# Sheet.net
KiCad netlist of a schematic drawn in Altium Designer
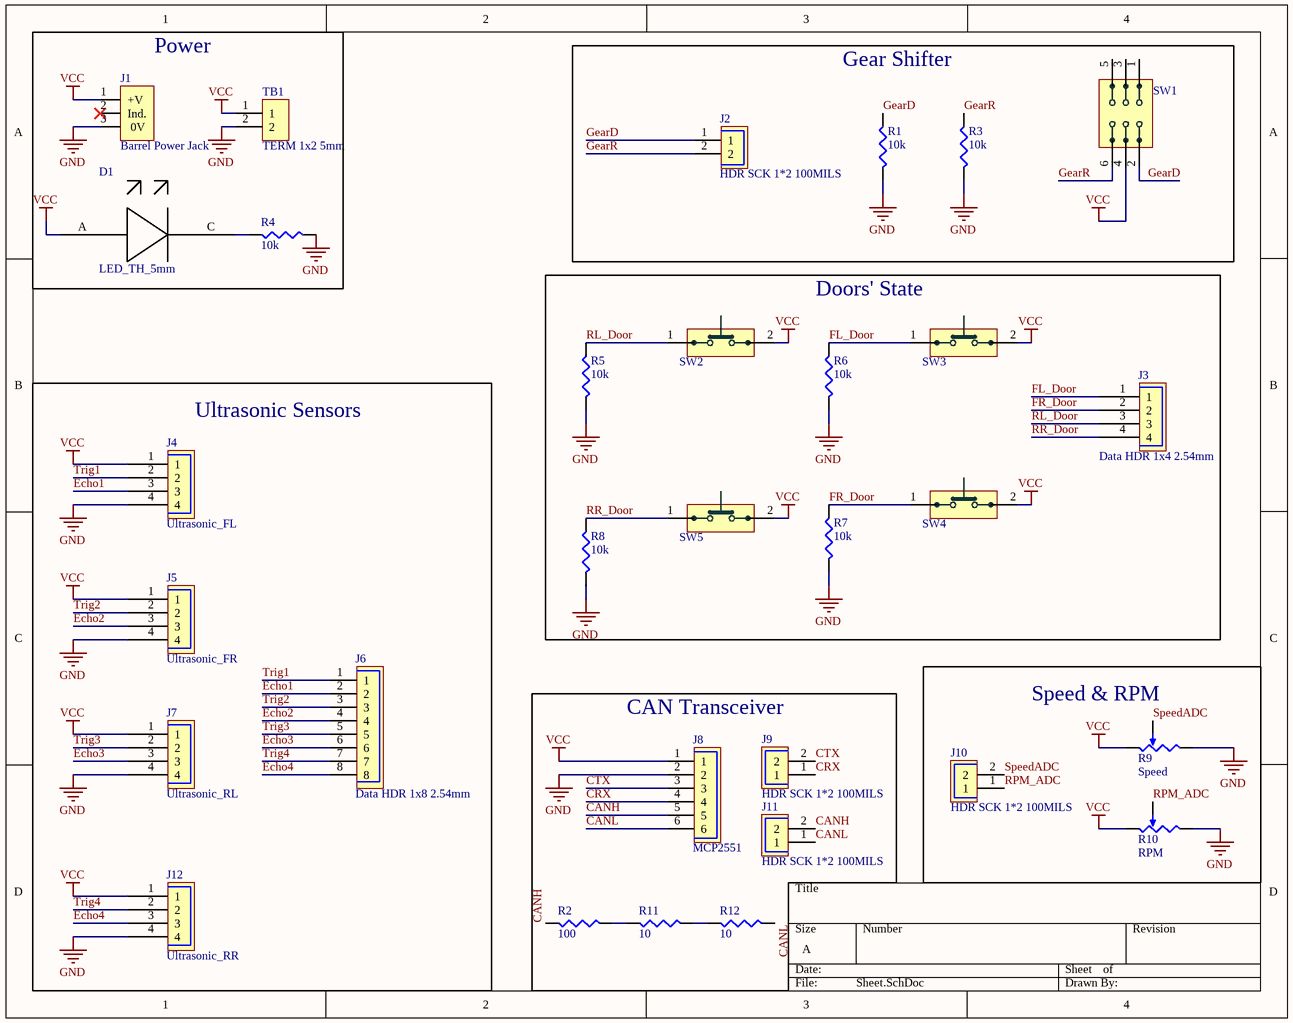
[diagram p0: Sheet.SchDoc]

(export (version "E")
  (design (tool "Eeschema 10.0.6"))
  (components
    (comp (ref "D1")
      (value "LED_TH_5mm")
      (footprint "LED_TH_5mm")
      (libsource (lib "Schlib") (part "LED_TH_5mm"))
    )
    (comp (ref "J1")
      (value "Barrel Power Jack")
      (footprint "pwr_Jack")
      (description "DC-Power Socket 12V 5A 2, 1mm Solder Eyel")
      (libsource (lib "CAD_Symbols") (part "Con-Jack"))
    )
    (comp (ref "J2")
      (value "HDR SCK 1*2 100MILS")
      (footprint "DHDR 1*2 2,54MM")
      (description "Conn Shrouded Header HDR 2 POS 2.54mm Solder ST Thru-Hole")
      (libsource (lib "") (part "2-Pin Data Connector_1"))
    )
    (comp (ref "J3")
      (value "Data HDR 1x4 2.54mm")
      (footprint "DHDR_1x4_2.54mm")
      (description "MTA-100 Series, 2.54mm Pitch 4 Way 1 RowStraight PCB Header, Solder Term, 5A")
      (libsource (lib "CAD_Symbols") (part "4-Pin Data Connector"))
    )
    (comp (ref "J4")
      (value "Ultrasonic_FL")
      (footprint "DHDR_1x4_2.54mm")
      (description "MTA-100 Series, 2.54mm Pitch 4 Way 1 RowStraight PCB Header, Solder Term, 5A")
      (libsource (lib "CAD_Symbols") (part "4-Pin Data Connector"))
    )
    (comp (ref "J5")
      (value "Ultrasonic_FR")
      (footprint "DHDR_1x4_2.54mm")
      (description "MTA-100 Series, 2.54mm Pitch 4 Way 1 RowStraight PCB Header, Solder Term, 5A")
      (libsource (lib "CAD_Symbols") (part "4-Pin Data Connector"))
    )
    (comp (ref "J6")
      (value "Data HDR 1x8 2.54mm")
      (footprint "DHDR_1x8_2.54mm")
      (description "CONN HEADER VERT 8POS .100 TIN")
      (libsource (lib "Schlib") (part "PinHeader_8Pin"))
    )
    (comp (ref "J7")
      (value "Ultrasonic_RL")
      (footprint "DHDR_1x4_2.54mm")
      (description "MTA-100 Series, 2.54mm Pitch 4 Way 1 RowStraight PCB Header, Solder Term, 5A")
      (libsource (lib "CAD_Symbols") (part "4-Pin Data Connector"))
    )
    (comp (ref "J8")
      (value "MCP2551")
      (footprint "DHDR_1x6_2.54mm")
      (description "CONN HEADER VERT 6POS .100 TIN")
      (libsource (lib "CAD_Symbols") (part "6-Pin Data Connector"))
    )
    (comp (ref "J9")
      (value "HDR SCK 1*2 100MILS")
      (footprint "DHDR 1*2 2,54MM")
      (description "Conn Shrouded Header HDR 2 POS 2.54mm Solder ST Thru-Hole")
      (libsource (lib "CAD_Symbols") (part "2-Pin Data Connector"))
    )
    (comp (ref "J10")
      (value "HDR SCK 1*2 100MILS")
      (footprint "DHDR 1*2 2,54MM")
      (description "Conn Shrouded Header HDR 2 POS 2.54mm Solder ST Thru-Hole")
      (libsource (lib "CAD_Symbols") (part "2-Pin Data Connector"))
    )
    (comp (ref "J11")
      (value "HDR SCK 1*2 100MILS")
      (footprint "DHDR 1*2 2,54MM")
      (description "Conn Shrouded Header HDR 2 POS 2.54mm Solder ST Thru-Hole")
      (libsource (lib "CAD_Symbols") (part "2-Pin Data Connector"))
    )
    (comp (ref "J12")
      (value "Ultrasonic_RR")
      (footprint "DHDR_1x4_2.54mm")
      (description "MTA-100 Series, 2.54mm Pitch 4 Way 1 RowStraight PCB Header, Solder Term, 5A")
      (libsource (lib "CAD_Symbols") (part "4-Pin Data Connector"))
    )
    (comp (ref "R1")
      (value "10k")
      (footprint "R_THT_CFR-25")
      (description "CFR Series 0.25 W 1 KOhm ±5 % -350 to 500 ppm/°C Carbon Film Resistor")
      (fields (field (name "TOLERANCE") "5%"))
      (libsource (lib "CAD_Symbols") (part "TH CFR-25 Resis"))
    )
    (comp (ref "R2")
      (value "100")
      (footprint "R_THT_CFR-25")
      (description "CFR Series 0.25 W 1 KOhm ±5 % -350 to 500 ppm/°C Carbon Film Resistor")
      (fields (field (name "TOLERANCE") "5%"))
      (libsource (lib "CAD_Symbols") (part "TH CFR-25 Resis"))
    )
    (comp (ref "R3")
      (value "10k")
      (footprint "R_THT_CFR-25")
      (description "CFR Series 0.25 W 1 KOhm ±5 % -350 to 500 ppm/°C Carbon Film Resistor")
      (fields (field (name "TOLERANCE") "5%"))
      (libsource (lib "CAD_Symbols") (part "TH CFR-25 Resis"))
    )
    (comp (ref "R4")
      (value "10k")
      (footprint "R_THT_CFR-25")
      (description "CFR Series 0.25 W 1 KOhm ±5 % -350 to 500 ppm/°C Carbon Film Resistor")
      (fields (field (name "TOLERANCE") "5%"))
      (libsource (lib "CAD_Symbols") (part "TH CFR-25 Resis"))
    )
    (comp (ref "R5")
      (value "10k")
      (footprint "R_THT_CFR-25")
      (description "CFR Series 0.25 W 1 KOhm ±5 % -350 to 500 ppm/°C Carbon Film Resistor")
      (fields (field (name "TOLERANCE") "5%"))
      (libsource (lib "CAD_Symbols") (part "TH CFR-25 Resis"))
    )
    (comp (ref "R6")
      (value "10k")
      (footprint "R_THT_CFR-25")
      (description "CFR Series 0.25 W 1 KOhm ±5 % -350 to 500 ppm/°C Carbon Film Resistor")
      (fields (field (name "TOLERANCE") "5%"))
      (libsource (lib "CAD_Symbols") (part "TH CFR-25 Resis"))
    )
    (comp (ref "R7")
      (value "10k")
      (footprint "R_THT_CFR-25")
      (description "CFR Series 0.25 W 1 KOhm ±5 % -350 to 500 ppm/°C Carbon Film Resistor")
      (fields (field (name "TOLERANCE") "5%"))
      (libsource (lib "CAD_Symbols") (part "TH CFR-25 Resis"))
    )
    (comp (ref "R8")
      (value "10k")
      (footprint "R_THT_CFR-25")
      (description "CFR Series 0.25 W 1 KOhm ±5 % -350 to 500 ppm/°C Carbon Film Resistor")
      (fields (field (name "TOLERANCE") "5%"))
      (libsource (lib "CAD_Symbols") (part "TH CFR-25 Resis"))
    )
    (comp (ref "R9") (value "Speed") (footprint "POT") (libsource (lib "CAD_Symbols") (part "POT")))
    (comp (ref "R10") (value "RPM") (footprint "POT") (libsource (lib "CAD_Symbols") (part "POT")))
    (comp (ref "R11")
      (value "10")
      (footprint "R_THT_CFR-25")
      (description "CFR Series 0.25 W 1 KOhm ±5 % -350 to 500 ppm/°C Carbon Film Resistor")
      (fields (field (name "TOLERANCE") "5%"))
      (libsource (lib "CAD_Symbols") (part "TH CFR-25 Resis"))
    )
    (comp (ref "R12")
      (value "10")
      (footprint "R_THT_CFR-25")
      (description "CFR Series 0.25 W 1 KOhm ±5 % -350 to 500 ppm/°C Carbon Film Resistor")
      (fields (field (name "TOLERANCE") "5%"))
      (libsource (lib "CAD_Symbols") (part "TH CFR-25 Resis"))
    )
    (comp (ref "SW1")
      (value "1825910-6")
      (footprint "DPDT_6Pin")
      (description "SWITCH TACTILE SPST-NO 0.05A 24V")
      (libsource (lib "Schlib") (part "DPDT_6Pin"))
    )
    (comp (ref "SW2")
      (value "1825910-6")
      (footprint "Push_Button_10mm_2Pin")
      (description "SWITCH TACTILE SPST-NO 0.05A 24V")
      (libsource (lib "Schlib") (part "Push_Button_10mm_2Pin"))
    )
    (comp (ref "SW3")
      (value "1825910-6")
      (footprint "Push_Button_10mm_2Pin")
      (description "SWITCH TACTILE SPST-NO 0.05A 24V")
      (libsource (lib "Schlib") (part "Push_Button_10mm_2Pin"))
    )
    (comp (ref "SW4")
      (value "1825910-6")
      (footprint "Push_Button_10mm_2Pin")
      (description "SWITCH TACTILE SPST-NO 0.05A 24V")
      (libsource (lib "Schlib") (part "Push_Button_10mm_2Pin"))
    )
    (comp (ref "SW5")
      (value "1825910-6")
      (footprint "Push_Button_10mm_2Pin")
      (description "SWITCH TACTILE SPST-NO 0.05A 24V")
      (libsource (lib "Schlib") (part "Push_Button_10mm_2Pin"))
    )
    (comp (ref "TB1")
      (value "TERM 1x2 5mm")
      (footprint "Terminal_5mm")
      (fields (field (name "VOLTAGE") "300V"))
      (libsource (lib "CAD_Symbols") (part "Terminal BLK Green"))
    )
  )
  (nets
    (net (code "1") (name "/CANH") (class "Default")
      (node (ref "J11") (pin "2") (pinfunction "2_2") (pintype "passive"))
      (node (ref "J8") (pin "5") (pinfunction "5_5") (pintype "passive"))
      (node (ref "R2") (pin "2") (pinfunction "2_2") (pintype "passive"))
    )
    (net (code "2") (name "/CANL") (class "Default")
      (node (ref "J11") (pin "1") (pinfunction "1_1") (pintype "passive"))
      (node (ref "J8") (pin "6") (pinfunction "6_6") (pintype "passive"))
      (node (ref "R12") (pin "1") (pinfunction "1_1") (pintype "passive"))
    )
    (net (code "3") (name "/CRX") (class "Default")
      (node (ref "J8") (pin "4") (pinfunction "4_4") (pintype "passive"))
      (node (ref "J9") (pin "1") (pinfunction "1_1") (pintype "passive"))
    )
    (net (code "4") (name "/CTX") (class "Default")
      (node (ref "J8") (pin "3") (pinfunction "3_3") (pintype "passive"))
      (node (ref "J9") (pin "2") (pinfunction "2_2") (pintype "passive"))
    )
    (net (code "5") (name "/Echo1") (class "Default")
      (node (ref "J4") (pin "3") (pinfunction "3_3") (pintype "passive"))
      (node (ref "J6") (pin "2") (pinfunction "2_2") (pintype "passive"))
    )
    (net (code "6") (name "/Echo2") (class "Default")
      (node (ref "J5") (pin "3") (pinfunction "3_3") (pintype "passive"))
      (node (ref "J6") (pin "4") (pinfunction "4_4") (pintype "passive"))
    )
    (net (code "7") (name "/Echo3") (class "Default")
      (node (ref "J6") (pin "6") (pinfunction "6_6") (pintype "passive"))
      (node (ref "J7") (pin "3") (pinfunction "3_3") (pintype "passive"))
    )
    (net (code "8") (name "/Echo4") (class "Default")
      (node (ref "J12") (pin "3") (pinfunction "3_3") (pintype "passive"))
      (node (ref "J6") (pin "8") (pinfunction "8_8") (pintype "passive"))
    )
    (net (code "9") (name "/FL_Door") (class "Default")
      (node (ref "J3") (pin "1") (pinfunction "1_1") (pintype "passive"))
      (node (ref "R6") (pin "2") (pinfunction "2_2") (pintype "passive"))
      (node (ref "SW3") (pin "1") (pinfunction "1_1") (pintype "passive"))
    )
    (net (code "10") (name "/FR_Door") (class "Default")
      (node (ref "J3") (pin "2") (pinfunction "2_2") (pintype "passive"))
      (node (ref "R7") (pin "2") (pinfunction "2_2") (pintype "passive"))
      (node (ref "SW4") (pin "1") (pinfunction "1_1") (pintype "passive"))
    )
    (net (code "11") (name "/GearD") (class "Default")
      (node (ref "J2") (pin "1") (pinfunction "1_1") (pintype "passive"))
      (node (ref "R1") (pin "2") (pinfunction "2_2") (pintype "passive"))
      (node (ref "SW1") (pin "2") (pinfunction "2_2") (pintype "passive"))
    )
    (net (code "12") (name "/GearR") (class "Default")
      (node (ref "J2") (pin "2") (pinfunction "2_2") (pintype "passive"))
      (node (ref "R3") (pin "2") (pinfunction "2_2") (pintype "passive"))
      (node (ref "SW1") (pin "6") (pinfunction "6_6") (pintype "passive"))
    )
    (net (code "13") (name "/RL_Door") (class "Default")
      (node (ref "J3") (pin "3") (pinfunction "3_3") (pintype "passive"))
      (node (ref "R5") (pin "2") (pinfunction "2_2") (pintype "passive"))
      (node (ref "SW2") (pin "1") (pinfunction "1_1") (pintype "passive"))
    )
    (net (code "14") (name "/RPM_ADC") (class "Default")
      (node (ref "J10") (pin "1") (pinfunction "1_1") (pintype "passive"))
      (node (ref "R10") (pin "3") (pinfunction "3_3") (pintype "passive"))
    )
    (net (code "15") (name "/RR_Door") (class "Default")
      (node (ref "J3") (pin "4") (pinfunction "4_4") (pintype "passive"))
      (node (ref "R8") (pin "2") (pinfunction "2_2") (pintype "passive"))
      (node (ref "SW5") (pin "1") (pinfunction "1_1") (pintype "passive"))
    )
    (net (code "16") (name "/SpeedADC") (class "Default")
      (node (ref "J10") (pin "2") (pinfunction "2_2") (pintype "passive"))
      (node (ref "R9") (pin "3") (pinfunction "3_3") (pintype "passive"))
    )
    (net (code "17") (name "/Trig1") (class "Default")
      (node (ref "J4") (pin "2") (pinfunction "2_2") (pintype "passive"))
      (node (ref "J6") (pin "1") (pinfunction "1_1") (pintype "passive"))
    )
    (net (code "18") (name "/Trig2") (class "Default")
      (node (ref "J5") (pin "2") (pinfunction "2_2") (pintype "passive"))
      (node (ref "J6") (pin "3") (pinfunction "3_3") (pintype "passive"))
    )
    (net (code "19") (name "/Trig3") (class "Default")
      (node (ref "J6") (pin "5") (pinfunction "5_5") (pintype "passive"))
      (node (ref "J7") (pin "2") (pinfunction "2_2") (pintype "passive"))
    )
    (net (code "20") (name "/Trig4") (class "Default")
      (node (ref "J12") (pin "2") (pinfunction "2_2") (pintype "passive"))
      (node (ref "J6") (pin "7") (pinfunction "7_7") (pintype "passive"))
    )
    (net (code "21") (name "GND") (class "Default")
      (node (ref "J1") (pin "3") (pinfunction "_0V_3") (pintype "passive"))
      (node (ref "J12") (pin "4") (pinfunction "4_4") (pintype "passive"))
      (node (ref "J4") (pin "4") (pinfunction "4_4") (pintype "passive"))
      (node (ref "J5") (pin "4") (pinfunction "4_4") (pintype "passive"))
      (node (ref "J7") (pin "4") (pinfunction "4_4") (pintype "passive"))
      (node (ref "J8") (pin "2") (pinfunction "2_2") (pintype "passive"))
      (node (ref "R1") (pin "1") (pinfunction "1_1") (pintype "passive"))
      (node (ref "R10") (pin "2") (pinfunction "2_2") (pintype "passive"))
      (node (ref "R3") (pin "1") (pinfunction "1_1") (pintype "passive"))
      (node (ref "R4") (pin "1") (pinfunction "1_1") (pintype "passive"))
      (node (ref "R5") (pin "1") (pinfunction "1_1") (pintype "passive"))
      (node (ref "R6") (pin "1") (pinfunction "1_1") (pintype "passive"))
      (node (ref "R7") (pin "1") (pinfunction "1_1") (pintype "passive"))
      (node (ref "R8") (pin "1") (pinfunction "1_1") (pintype "passive"))
      (node (ref "R9") (pin "2") (pinfunction "2_2") (pintype "passive"))
      (node (ref "TB1") (pin "2") (pinfunction "2_2") (pintype "passive"))
    )
    (net (code "22") (name "Net-(D1-PadC)") (class "Default")
      (node (ref "D1") (pin "C") (pinfunction "C_C") (pintype "passive"))
      (node (ref "R4") (pin "2") (pinfunction "2_2") (pintype "passive"))
    )
    (net (code "23") (name "Net-(R11-Pad1)") (class "Default")
      (node (ref "R11") (pin "1") (pinfunction "1_1") (pintype "passive"))
      (node (ref "R12") (pin "2") (pinfunction "2_2") (pintype "passive"))
    )
    (net (code "24") (name "Net-(R11-Pad2)") (class "Default")
      (node (ref "R11") (pin "2") (pinfunction "2_2") (pintype "passive"))
      (node (ref "R2") (pin "1") (pinfunction "1_1") (pintype "passive"))
    )
    (net (code "25") (name "VCC") (class "Default")
      (node (ref "D1") (pin "A") (pinfunction "A_A") (pintype "passive"))
      (node (ref "J1") (pin "1") (pinfunction "+V_1") (pintype "passive"))
      (node (ref "J12") (pin "1") (pinfunction "1_1") (pintype "passive"))
      (node (ref "J4") (pin "1") (pinfunction "1_1") (pintype "passive"))
      (node (ref "J5") (pin "1") (pinfunction "1_1") (pintype "passive"))
      (node (ref "J7") (pin "1") (pinfunction "1_1") (pintype "passive"))
      (node (ref "J8") (pin "1") (pinfunction "1_1") (pintype "passive"))
      (node (ref "R10") (pin "1") (pinfunction "1_1") (pintype "passive"))
      (node (ref "R9") (pin "1") (pinfunction "1_1") (pintype "passive"))
      (node (ref "SW1") (pin "4") (pinfunction "4_4") (pintype "passive"))
      (node (ref "SW2") (pin "2") (pinfunction "2_2") (pintype "passive"))
      (node (ref "SW3") (pin "2") (pinfunction "2_2") (pintype "passive"))
      (node (ref "SW4") (pin "2") (pinfunction "2_2") (pintype "passive"))
      (node (ref "SW5") (pin "2") (pinfunction "2_2") (pintype "passive"))
      (node (ref "TB1") (pin "1") (pinfunction "1_1") (pintype "passive"))
    )
    (net (code "26") (name "unconnected-(J1-Ind.-Pad2)") (class "Default")
      (node (ref "J1") (pin "2") (pinfunction "Ind._2") (pintype "passive+no_connect"))
    )
    (net (code "27") (name "unconnected-(SW1-Pad1)") (class "Default")
      (node (ref "SW1") (pin "1") (pinfunction "1_1") (pintype "passive"))
    )
    (net (code "28") (name "unconnected-(SW1-Pad3)") (class "Default")
      (node (ref "SW1") (pin "3") (pinfunction "3_3") (pintype "passive"))
    )
    (net (code "29") (name "unconnected-(SW1-Pad5)") (class "Default")
      (node (ref "SW1") (pin "5") (pinfunction "5_5") (pintype "passive"))
    )
  )
)
